# GPS.net
KiCad netlist of a schematic drawn in Altium Designer
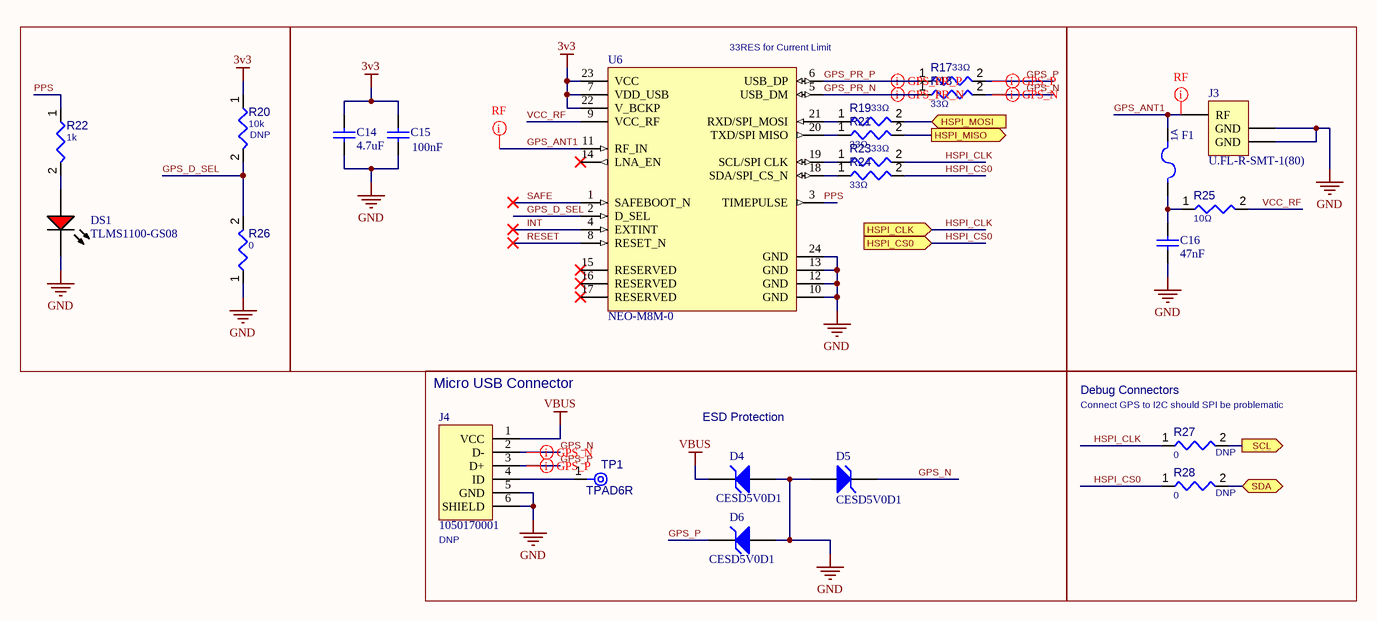
[diagram p0: GPS.SchDoc]

(export (version "E")
  (design (tool "Eeschema 10.0.6"))
  (components
    (comp (ref "C14")
      (value "GRM155R60J475ME87D")
      (footprint "Capacitor_0402")
      (description "6.3V 4.7uF X5R ±20% 0402 Multilayer Ceramic Capacitors MLCC - SMD/SMT ROHS")
      (fields (field (name "CAPACITANCE") "4.7uF") (field (name "TOLERANCE") "20%"))
      (libsource (lib "RIT Launch Initiative") (part "CAPACITOR"))
    )
    (comp (ref "C15")
      (value "GRM155R71E104KE14D")
      (footprint "Capacitor_0402")
      (description "Chip Capacitor 100nF 0402 25V X7R")
      (fields (field (name "CAPACITANCE") "100nF"))
      (libsource (lib "RIT Launch Initiative") (part "CAPACITOR"))
    )
    (comp (ref "C16")
      (value "GCM155R71H473KE02J")
      (footprint "Capacitor_0402")
      (description "Cap Ceramic 47nF 50V X7R 10% Pad SMD 0402 125C Automotive T/R")
      (fields (field (name "CAPACITANCE") "47nF") (field (name "JLCPCB PART #") "C697422"))
      (libsource (lib "RIT Launch Initiative") (part "CAPACITOR"))
    )
    (comp (ref "D4")
      (value "CESD5V0D1")
      (footprint "JSCJ-SOD-123-2_V")
      (description "Uni-driection ESD Protection Diode, 5 V, 1 uA, 2-Pin SOD-123, RoHS, Tape and Reel")
      (fields (field (name "MANUFACTURER") "Jiangsu Changjiang Electronics Technology"))
      (libsource (lib "RIT Launch Initiative") (part "DZEN-AK-2"))
    )
    (comp (ref "D5")
      (value "CESD5V0D1")
      (footprint "JSCJ-SOD-123-2_V")
      (description "Uni-driection ESD Protection Diode, 5 V, 1 uA, 2-Pin SOD-123, RoHS, Tape and Reel")
      (fields (field (name "MANUFACTURER") "Jiangsu Changjiang Electronics Technology"))
      (libsource (lib "RIT Launch Initiative") (part "DZEN-AK-2"))
    )
    (comp (ref "D6")
      (value "CESD5V0D1")
      (footprint "JSCJ-SOD-123-2_V")
      (description "Uni-driection ESD Protection Diode, 5 V, 1 uA, 2-Pin SOD-123, RoHS, Tape and Reel")
      (fields (field (name "MANUFACTURER") "Jiangsu Changjiang Electronics Technology"))
      (libsource (lib "RIT Launch Initiative") (part "DZEN-AK-2"))
    )
    (comp (ref "DS1")
      (value "TLMS1100-GS08")
      (footprint "VISH-TLMX1100_V")
      (description "Red Led, 20mA, 2.1 V, -40 to 100 degC, 2-Pin SMD (0603), RoHS, Tape and Reel")
      (fields (field (name "MANUFACTURER") "Vishay Semiconductor") (field (name "POWER") "90mW"))
      (libsource (lib "RIT Launch Initiative") (part "LED-RED-AK-2"))
    )
    (comp (ref "F1")
      (value "0466001.NRHF")
      (footprint "FP-0466-MFG")
      (description "Fuse Chip Very Fast Acting 1A 63V SMD Solder Pad 1206 T/R CSA")
      (fields (field (name "JLCPCB PART #") "C151135"))
      (libsource (lib "RIT Launch Initiative") (part "FUSE"))
    )
    (comp (ref "J3")
      (value "U.FL-R-SMT-1(80)")
      (footprint "FP-U_FL-R-SMT-1_80-MFG")
      (description "CONN U.FL RCPT STR 50 OHM SMD")
      (fields (field (name "JLCPCB PART #") "C88374"))
      (libsource (lib "RIT Launch Initiative") (part "U.FL-R-SMT-1(80)"))
    )
    (comp (ref "J4")
      (value "1050170001")
      (footprint "1050170001-Footprint-1")
      (description "Micro USB Connector; Data Recept.; Micro; B Type; Bottom Mount, SMT, with Solder Tabs, Lead-Free")
      (fields (field (name "DNP") "DNP") (field (name "JLCPCB PART #") "C136000"))
      (libsource (lib "RIT Launch Initiative") (part "1050170001"))
    )
    (comp (ref "R17")
      (value "33Ω")
      (footprint "RESC0402(1005)_L")
      (description "33R 0.063W 5% 0402 (1005 Metric)  SMD")
      (fields (field (name "TOLERANCE") "5%") (field (name "POWER") "63mW"))
      (libsource (lib "RIT Launch Initiative") (part "33R2J"))
    )
    (comp (ref "R18")
      (value "33Ω")
      (footprint "RESC0402(1005)_L")
      (description "33R 0.063W 5% 0402 (1005 Metric)  SMD")
      (fields (field (name "TOLERANCE") "5%") (field (name "POWER") "63mW"))
      (libsource (lib "RIT Launch Initiative") (part "33R2J"))
    )
    (comp (ref "R19")
      (value "33Ω")
      (footprint "RESC0402(1005)_L")
      (description "33R 0.063W 5% 0402 (1005 Metric)  SMD")
      (fields (field (name "TOLERANCE") "5%") (field (name "POWER") "63mW"))
      (libsource (lib "RIT Launch Initiative") (part "33R2J"))
    )
    (comp (ref "R20")
      (value "10k")
      (footprint "RESC0402(1005)_L")
      (description "Chip Resistor, 10 kOhms, +/-1 %, 63 mW, -55 to 125 degC, 0402")
      (fields (field (name "POWER") "63mW") (field (name "TOLERANCE") "1%") (field (name "DNP") "DNP"))
      (libsource (lib "RIT Launch Initiative") (part "RES-2"))
    )
    (comp (ref "R21")
      (value "33Ω")
      (footprint "RESC0402(1005)_L")
      (description "33R 0.063W 5% 0402 (1005 Metric)  SMD")
      (fields (field (name "TOLERANCE") "5%") (field (name "POWER") "63mW"))
      (libsource (lib "RIT Launch Initiative") (part "33R2J"))
    )
    (comp (ref "R22")
      (value "1k")
      (footprint "RESC0402(1005)_L")
      (description "Chip Resistor, 1 kOhms, +/-5 %, 63 mW, -55 to 155 degC, 0402")
      (fields (field (name "POWER") "63mW") (field (name "TOLERANCE") "5%"))
      (libsource (lib "RIT Launch Initiative") (part "RES-2"))
    )
    (comp (ref "R23")
      (value "33Ω")
      (footprint "RESC0402(1005)_L")
      (description "33R 0.063W 5% 0402 (1005 Metric)  SMD")
      (fields (field (name "TOLERANCE") "5%") (field (name "POWER") "63mW"))
      (libsource (lib "RIT Launch Initiative") (part "33R2J"))
    )
    (comp (ref "R24")
      (value "33Ω")
      (footprint "RESC0402(1005)_L")
      (description "33R 0.063W 5% 0402 (1005 Metric)  SMD")
      (fields (field (name "TOLERANCE") "5%") (field (name "POWER") "63mW"))
      (libsource (lib "RIT Launch Initiative") (part "33R2J"))
    )
    (comp (ref "R25")
      (value "10Ω")
      (footprint "RESC0402(1005)_L")
      (description "10R 0.063W 1% 0402 (1005 Metric)  SMD")
      (fields (field (name "POWER") "63mW") (field (name "TOLERANCE") "1%"))
      (libsource (lib "RIT Launch Initiative") (part "10R2F"))
    )
    (comp (ref "R26")
      (value "0")
      (footprint "RESC0402(1005)_L")
      (description "Jumper 0402")
      (libsource (lib "RIT Launch Initiative") (part "RES-2"))
    )
    (comp (ref "R27")
      (value "0")
      (footprint "RESC0402(1005)_L")
      (description "Jumper 0402")
      (fields (field (name "DNP") "DNP"))
      (libsource (lib "RIT Launch Initiative") (part "RES-2"))
    )
    (comp (ref "R28")
      (value "0")
      (footprint "RESC0402(1005)_L")
      (description "Jumper 0402")
      (fields (field (name "DNP") "DNP"))
      (libsource (lib "RIT Launch Initiative") (part "RES-2"))
    )
    (comp (ref "TP1")
      (value "TPAD6R")
      (footprint "TP06R")
      (description "0.6mm round")
      (libsource (lib "RIT Launch Initiative") (part "CMP-001-0001-4"))
    )
    (comp (ref "U6")
      (value "NEO-M8M-0")
      (footprint "NEO-M8M-0-Footprint-1")
      (description "GPS RF Receiver BeiDou, Galileo, GLONASS, GNSS, GPS 1.575GHz -167dBm")
      (libsource (lib "RIT Launch Initiative") (part "NEO-M8M-0-Symbol-1"))
    )
  )
  (nets
    (net (code "1") (name "/GPS_ANT1") (class "Default")
      (node (ref "F1") (pin "2") (pinfunction "2_2") (pintype "passive"))
      (node (ref "J3") (pin "1") (pinfunction "RF_1") (pintype "passive"))
      (node (ref "U6") (pin "11") (pinfunction "RF_IN_11") (pintype "input"))
    )
    (net (code "2") (name "/GPS_D_SEL") (class "Default")
      (node (ref "R20") (pin "2") (pinfunction "2_2") (pintype "passive"))
      (node (ref "R26") (pin "2") (pinfunction "2_2") (pintype "passive"))
      (node (ref "U6") (pin "2") (pinfunction "D_SEL_2") (pintype "input"))
    )
    (net (code "3") (name "/GPS_N") (class "Default")
      (node (ref "D5") (pin "2") (pinfunction "K_2") (pintype "passive"))
      (node (ref "J4") (pin "2") (pinfunction "D-_2") (pintype "passive"))
      (node (ref "R18") (pin "2") (pinfunction "2_2") (pintype "passive"))
    )
    (net (code "4") (name "/GPS_P") (class "Default")
      (node (ref "D6") (pin "2") (pinfunction "K_2") (pintype "passive"))
      (node (ref "J4") (pin "3") (pinfunction "D+_3") (pintype "passive"))
      (node (ref "R17") (pin "2") (pinfunction "2_2") (pintype "passive"))
    )
    (net (code "5") (name "/GPS_PR_N") (class "Default")
      (node (ref "R18") (pin "1") (pinfunction "1_1") (pintype "passive"))
      (node (ref "U6") (pin "5") (pinfunction "USB_DM_5") (pintype "bidirectional"))
    )
    (net (code "6") (name "/GPS_PR_P") (class "Default")
      (node (ref "R17") (pin "1") (pinfunction "1_1") (pintype "passive"))
      (node (ref "U6") (pin "6") (pinfunction "USB_DP_6") (pintype "bidirectional"))
    )
    (net (code "7") (name "/HSPI_CLK") (class "Default")
      (node (ref "R23") (pin "2") (pinfunction "2_2") (pintype "passive"))
      (node (ref "R27") (pin "1") (pinfunction "1_1") (pintype "passive"))
    )
    (net (code "8") (name "/HSPI_CS0") (class "Default")
      (node (ref "R24") (pin "2") (pinfunction "2_2") (pintype "passive"))
      (node (ref "R28") (pin "1") (pinfunction "1_1") (pintype "passive"))
    )
    (net (code "9") (name "/HSPI_MISO") (class "Default")
      (node (ref "R21") (pin "2") (pinfunction "2_2") (pintype "passive"))
    )
    (net (code "10") (name "/HSPI_MOSI") (class "Default")
      (node (ref "R19") (pin "2") (pinfunction "2_2") (pintype "passive"))
    )
    (net (code "11") (name "/INT") (class "Default")
      (node (ref "U6") (pin "4") (pinfunction "EXTINT_4") (pintype "input+no_connect"))
    )
    (net (code "12") (name "/PPS") (class "Default")
      (node (ref "R22") (pin "1") (pinfunction "1_1") (pintype "passive"))
      (node (ref "U6") (pin "3") (pinfunction "TIMEPULSE_3") (pintype "output"))
    )
    (net (code "13") (name "/RESET") (class "Default")
      (node (ref "U6") (pin "8") (pinfunction "RESET_N_8") (pintype "input+no_connect"))
    )
    (net (code "14") (name "/SAFE") (class "Default")
      (node (ref "U6") (pin "1") (pinfunction "SAFEBOOT_N_1") (pintype "input+no_connect"))
    )
    (net (code "15") (name "/SCL") (class "Default")
      (node (ref "R27") (pin "2") (pinfunction "2_2") (pintype "passive"))
    )
    (net (code "16") (name "/SDA") (class "Default")
      (node (ref "R28") (pin "2") (pinfunction "2_2") (pintype "passive"))
    )
    (net (code "17") (name "/VCC_RF") (class "Default")
      (node (ref "R25") (pin "2") (pinfunction "2_2") (pintype "passive"))
      (node (ref "U6") (pin "9") (pinfunction "VCC_RF_9") (pintype "power_in"))
    )
    (net (code "18") (name "3v3") (class "Default")
      (node (ref "C14") (pin "2") (pinfunction "2_2") (pintype "passive"))
      (node (ref "C15") (pin "2") (pinfunction "2_2") (pintype "passive"))
      (node (ref "R20") (pin "1") (pinfunction "1_1") (pintype "passive"))
      (node (ref "U6") (pin "22") (pinfunction "V_BCKP_22") (pintype "power_in"))
      (node (ref "U6") (pin "23") (pinfunction "VCC_23") (pintype "power_in"))
      (node (ref "U6") (pin "7") (pinfunction "VDD_USB_7") (pintype "power_in"))
    )
    (net (code "19") (name "GND") (class "Default")
      (node (ref "C14") (pin "1") (pinfunction "1_1") (pintype "passive"))
      (node (ref "C15") (pin "1") (pinfunction "1_1") (pintype "passive"))
      (node (ref "C16") (pin "1") (pinfunction "1_1") (pintype "passive"))
      (node (ref "D4") (pin "1") (pinfunction "A_1") (pintype "passive"))
      (node (ref "D5") (pin "1") (pinfunction "A_1") (pintype "passive"))
      (node (ref "D6") (pin "1") (pinfunction "A_1") (pintype "passive"))
      (node (ref "DS1") (pin "2") (pinfunction "K_2") (pintype "passive"))
      (node (ref "J3") (pin "2") (pinfunction "GND_2") (pintype "power_in"))
      (node (ref "J3") (pin "3") (pinfunction "GND_3") (pintype "power_in"))
      (node (ref "J4") (pin "5") (pinfunction "GND_5") (pintype "passive"))
      (node (ref "J4") (pin "6") (pinfunction "SHIELD_6") (pintype "passive"))
      (node (ref "R26") (pin "1") (pinfunction "1_1") (pintype "passive"))
      (node (ref "U6") (pin "10") (pinfunction "GND_10") (pintype "power_in"))
      (node (ref "U6") (pin "12") (pinfunction "GND_12") (pintype "power_in"))
      (node (ref "U6") (pin "13") (pinfunction "GND_13") (pintype "power_in"))
      (node (ref "U6") (pin "24") (pinfunction "GND_24") (pintype "power_in"))
    )
    (net (code "20") (name "Net-(C16-Pad2)") (class "Default")
      (node (ref "C16") (pin "2") (pinfunction "2_2") (pintype "passive"))
      (node (ref "F1") (pin "1") (pinfunction "1_1") (pintype "passive"))
      (node (ref "R25") (pin "1") (pinfunction "1_1") (pintype "passive"))
    )
    (net (code "21") (name "Net-(DS1-A)") (class "Default")
      (node (ref "DS1") (pin "1") (pinfunction "A_1") (pintype "passive"))
      (node (ref "R22") (pin "2") (pinfunction "2_2") (pintype "passive"))
    )
    (net (code "22") (name "Net-(J4-ID)") (class "Default")
      (node (ref "J4") (pin "4") (pinfunction "ID_4") (pintype "passive"))
      (node (ref "TP1") (pin "1") (pinfunction "TP_1") (pintype "passive"))
    )
    (net (code "23") (name "Net-(U6-RXD{slash}SPI_MOSI)") (class "Default")
      (node (ref "R19") (pin "1") (pinfunction "1_1") (pintype "passive"))
      (node (ref "U6") (pin "21") (pinfunction "RXD/SPI_MOSI_21") (pintype "input"))
    )
    (net (code "24") (name "Net-(U6-SCL{slash}SPI_CLK)") (class "Default")
      (node (ref "R23") (pin "1") (pinfunction "1_1") (pintype "passive"))
      (node (ref "U6") (pin "19") (pinfunction "SCL/SPI_CLK_19") (pintype "bidirectional"))
    )
    (net (code "25") (name "Net-(U6-SDA{slash}SPI_CS_N)") (class "Default")
      (node (ref "R24") (pin "1") (pinfunction "1_1") (pintype "passive"))
      (node (ref "U6") (pin "18") (pinfunction "SDA/SPI_CS_N_18") (pintype "bidirectional"))
    )
    (net (code "26") (name "Net-(U6-TXD{slash}SPI_MISO)") (class "Default")
      (node (ref "R21") (pin "1") (pinfunction "1_1") (pintype "passive"))
      (node (ref "U6") (pin "20") (pinfunction "TXD/SPI_MISO_20") (pintype "output"))
    )
    (net (code "27") (name "VBUS") (class "Default")
      (node (ref "D4") (pin "2") (pinfunction "K_2") (pintype "passive"))
      (node (ref "J4") (pin "1") (pinfunction "VCC_1") (pintype "passive"))
    )
    (net (code "28") (name "unconnected-(U6-LNA_EN-Pad14)") (class "Default")
      (node (ref "U6") (pin "14") (pinfunction "LNA_EN_14") (pintype "output+no_connect"))
    )
    (net (code "29") (name "unconnected-(U6-RESERVED-Pad15)") (class "Default")
      (node (ref "U6") (pin "15") (pinfunction "RESERVED_15") (pintype "passive+no_connect"))
    )
    (net (code "30") (name "unconnected-(U6-RESERVED-Pad16)") (class "Default")
      (node (ref "U6") (pin "16") (pinfunction "RESERVED_16") (pintype "passive+no_connect"))
    )
    (net (code "31") (name "unconnected-(U6-RESERVED-Pad17)") (class "Default")
      (node (ref "U6") (pin "17") (pinfunction "RESERVED_17") (pintype "passive+no_connect"))
    )
  )
)
